# Sheet1.net
KiCad netlist of a schematic drawn in Altium Designer
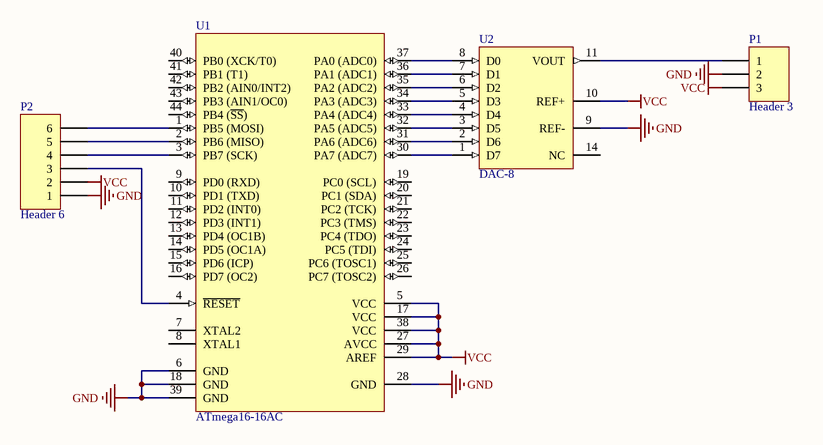
[diagram p0: Sheet1.SchDoc]

(export (version "E")
  (design (tool "Eeschema 10.0.6"))
  (components
    (comp (ref "P1")
      (value "Header 3")
      (footprint "HDR1X3")
      (description "Header, 3-Pin")
      (fields (field (name "PUBLISHER") "Altium Limited"))
      (libsource (lib "Miscellaneous Connectors") (part "Header 3"))
    )
    (comp (ref "P2")
      (value "Header 6")
      (footprint "HDR1X6")
      (description "Header, 6-Pin")
      (fields (field (name "PUBLISHER") "Altium Limited"))
      (libsource (lib "Miscellaneous Connectors") (part "Header 6"))
    )
    (comp (ref "U1")
      (value "ATmega16-16AC")
      (footprint "44A_N")
      (description "8-Bit AVR Microcontroller with 16K Bytes of In-System Programmable Flash Memory")
      (fields (field (name "PUBLISHER") "Altium Limited"))
      (libsource (lib "Atmel Microcontroller 8-Bit AVR") (part "ATmega16-16AC"))
    )
    (comp (ref "U2")
      (value "DAC-8")
      (footprint "SOT402-1_N")
      (description "Generic 8-Bit D/A Converter")
      (fields (field (name "PUBLISHER") "Altium Limited"))
      (libsource (lib "Miscellaneous Devices") (part "DAC-8"))
    )
  )
  (nets
    (net (code "1") (name "GND") (class "Default")
      (node (ref "P1") (pin "2") (pinfunction "2_2") (pintype "passive"))
      (node (ref "P2") (pin "1") (pinfunction "1_1") (pintype "passive"))
      (node (ref "U1") (pin "18") (pinfunction "GND_18") (pintype "power_in"))
      (node (ref "U1") (pin "28") (pinfunction "GND_28") (pintype "power_in"))
      (node (ref "U1") (pin "39") (pinfunction "GND_39") (pintype "power_in"))
      (node (ref "U1") (pin "6") (pinfunction "GND_6") (pintype "power_in"))
      (node (ref "U2") (pin "12") (pinfunction "GND_12") (pintype "power_in"))
      (node (ref "U2") (pin "9") (pinfunction "REF-_9") (pintype "passive"))
    )
    (net (code "2") (name "Net-(U1-PA0_(ADC0))") (class "Default")
      (node (ref "U1") (pin "37") (pinfunction "PA0_(ADC0)_37") (pintype "bidirectional"))
      (node (ref "U2") (pin "8") (pinfunction "D0_8") (pintype "input"))
    )
    (net (code "3") (name "Net-(U1-PA1_(ADC1))") (class "Default")
      (node (ref "U1") (pin "36") (pinfunction "PA1_(ADC1)_36") (pintype "bidirectional"))
      (node (ref "U2") (pin "7") (pinfunction "D1_7") (pintype "input"))
    )
    (net (code "4") (name "Net-(U1-PA2_(ADC2))") (class "Default")
      (node (ref "U1") (pin "35") (pinfunction "PA2_(ADC2)_35") (pintype "bidirectional"))
      (node (ref "U2") (pin "6") (pinfunction "D2_6") (pintype "input"))
    )
    (net (code "5") (name "Net-(U1-PA3_(ADC3))") (class "Default")
      (node (ref "U1") (pin "34") (pinfunction "PA3_(ADC3)_34") (pintype "bidirectional"))
      (node (ref "U2") (pin "5") (pinfunction "D3_5") (pintype "input"))
    )
    (net (code "6") (name "Net-(U1-PA4_(ADC4))") (class "Default")
      (node (ref "U1") (pin "33") (pinfunction "PA4_(ADC4)_33") (pintype "bidirectional"))
      (node (ref "U2") (pin "4") (pinfunction "D4_4") (pintype "input"))
    )
    (net (code "7") (name "Net-(U1-PA5_(ADC5))") (class "Default")
      (node (ref "U1") (pin "32") (pinfunction "PA5_(ADC5)_32") (pintype "bidirectional"))
      (node (ref "U2") (pin "3") (pinfunction "D5_3") (pintype "input"))
    )
    (net (code "8") (name "Net-(U1-PA6_(ADC6))") (class "Default")
      (node (ref "U1") (pin "31") (pinfunction "PA6_(ADC6)_31") (pintype "bidirectional"))
      (node (ref "U2") (pin "2") (pinfunction "D6_2") (pintype "input"))
    )
    (net (code "9") (name "Net-(U1-PA7_(ADC7))") (class "Default")
      (node (ref "U1") (pin "30") (pinfunction "PA7_(ADC7)_30") (pintype "bidirectional"))
      (node (ref "U2") (pin "1") (pinfunction "D7_1") (pintype "input"))
    )
    (net (code "10") (name "Net-(U1-PB5_(MOSI))") (class "Default")
      (node (ref "P2") (pin "6") (pinfunction "6_6") (pintype "passive"))
      (node (ref "U1") (pin "1") (pinfunction "PB5_(MOSI)_1") (pintype "bidirectional"))
    )
    (net (code "11") (name "Net-(U1-PB6_(MISO))") (class "Default")
      (node (ref "P2") (pin "5") (pinfunction "5_5") (pintype "passive"))
      (node (ref "U1") (pin "2") (pinfunction "PB6_(MISO)_2") (pintype "bidirectional"))
    )
    (net (code "12") (name "Net-(U1-PB7_(SCK))") (class "Default")
      (node (ref "P2") (pin "4") (pinfunction "4_4") (pintype "passive"))
      (node (ref "U1") (pin "3") (pinfunction "PB7_(SCK)_3") (pintype "bidirectional"))
    )
    (net (code "13") (name "Net-(U1-~{RESET})") (class "Default")
      (node (ref "P2") (pin "3") (pinfunction "3_3") (pintype "passive"))
      (node (ref "U1") (pin "4") (pinfunction "~{RESET}_4") (pintype "input"))
    )
    (net (code "14") (name "Net-(U2-VOUT)") (class "Default")
      (node (ref "P1") (pin "1") (pinfunction "1_1") (pintype "passive"))
      (node (ref "U2") (pin "11") (pinfunction "VOUT_11") (pintype "output"))
    )
    (net (code "15") (name "VCC") (class "Default")
      (node (ref "P1") (pin "3") (pinfunction "3_3") (pintype "passive"))
      (node (ref "P2") (pin "2") (pinfunction "2_2") (pintype "passive"))
      (node (ref "U1") (pin "17") (pinfunction "VCC_17") (pintype "power_in"))
      (node (ref "U1") (pin "27") (pinfunction "AVCC_27") (pintype "power_in"))
      (node (ref "U1") (pin "29") (pinfunction "AREF_29") (pintype "passive"))
      (node (ref "U1") (pin "38") (pinfunction "VCC_38") (pintype "power_in"))
      (node (ref "U1") (pin "5") (pinfunction "VCC_5") (pintype "power_in"))
      (node (ref "U2") (pin "10") (pinfunction "REF+_10") (pintype "passive"))
      (node (ref "U2") (pin "13") (pinfunction "VCC_13") (pintype "power_in"))
    )
    (net (code "16") (name "unconnected-(U1-PB0_(XCK{slash}T0)-Pad40)") (class "Default")
      (node (ref "U1") (pin "40") (pinfunction "PB0_(XCK/T0)_40") (pintype "bidirectional"))
    )
    (net (code "17") (name "unconnected-(U1-PB1_(T1)-Pad41)") (class "Default")
      (node (ref "U1") (pin "41") (pinfunction "PB1_(T1)_41") (pintype "bidirectional"))
    )
    (net (code "18") (name "unconnected-(U1-PB2_(AIN0{slash}INT2)-Pad42)") (class "Default")
      (node (ref "U1") (pin "42") (pinfunction "PB2_(AIN0/INT2)_42") (pintype "bidirectional"))
    )
    (net (code "19") (name "unconnected-(U1-PB3_(AIN1{slash}OC0)-Pad43)") (class "Default")
      (node (ref "U1") (pin "43") (pinfunction "PB3_(AIN1/OC0)_43") (pintype "bidirectional"))
    )
    (net (code "20") (name "unconnected-(U1-PB4_(~{SS})-Pad44)") (class "Default")
      (node (ref "U1") (pin "44") (pinfunction "PB4_(~{SS})_44") (pintype "bidirectional"))
    )
    (net (code "21") (name "unconnected-(U1-PC0_(SCL)-Pad19)") (class "Default")
      (node (ref "U1") (pin "19") (pinfunction "PC0_(SCL)_19") (pintype "bidirectional"))
    )
    (net (code "22") (name "unconnected-(U1-PC1_(SDA)-Pad20)") (class "Default")
      (node (ref "U1") (pin "20") (pinfunction "PC1_(SDA)_20") (pintype "bidirectional"))
    )
    (net (code "23") (name "unconnected-(U1-PC2_(TCK)-Pad21)") (class "Default")
      (node (ref "U1") (pin "21") (pinfunction "PC2_(TCK)_21") (pintype "bidirectional"))
    )
    (net (code "24") (name "unconnected-(U1-PC3_(TMS)-Pad22)") (class "Default")
      (node (ref "U1") (pin "22") (pinfunction "PC3_(TMS)_22") (pintype "bidirectional"))
    )
    (net (code "25") (name "unconnected-(U1-PC4_(TDO)-Pad23)") (class "Default")
      (node (ref "U1") (pin "23") (pinfunction "PC4_(TDO)_23") (pintype "bidirectional"))
    )
    (net (code "26") (name "unconnected-(U1-PC5_(TDI)-Pad24)") (class "Default")
      (node (ref "U1") (pin "24") (pinfunction "PC5_(TDI)_24") (pintype "bidirectional"))
    )
    (net (code "27") (name "unconnected-(U1-PC6_(TOSC1)-Pad25)") (class "Default")
      (node (ref "U1") (pin "25") (pinfunction "PC6_(TOSC1)_25") (pintype "bidirectional"))
    )
    (net (code "28") (name "unconnected-(U1-PC7_(TOSC2)-Pad26)") (class "Default")
      (node (ref "U1") (pin "26") (pinfunction "PC7_(TOSC2)_26") (pintype "bidirectional"))
    )
    (net (code "29") (name "unconnected-(U1-PD0_(RXD)-Pad9)") (class "Default")
      (node (ref "U1") (pin "9") (pinfunction "PD0_(RXD)_9") (pintype "bidirectional"))
    )
    (net (code "30") (name "unconnected-(U1-PD1_(TXD)-Pad10)") (class "Default")
      (node (ref "U1") (pin "10") (pinfunction "PD1_(TXD)_10") (pintype "bidirectional"))
    )
    (net (code "31") (name "unconnected-(U1-PD2_(INT0)-Pad11)") (class "Default")
      (node (ref "U1") (pin "11") (pinfunction "PD2_(INT0)_11") (pintype "bidirectional"))
    )
    (net (code "32") (name "unconnected-(U1-PD3_(INT1)-Pad12)") (class "Default")
      (node (ref "U1") (pin "12") (pinfunction "PD3_(INT1)_12") (pintype "bidirectional"))
    )
    (net (code "33") (name "unconnected-(U1-PD4_(OC1B)-Pad13)") (class "Default")
      (node (ref "U1") (pin "13") (pinfunction "PD4_(OC1B)_13") (pintype "bidirectional"))
    )
    (net (code "34") (name "unconnected-(U1-PD5_(OC1A)-Pad14)") (class "Default")
      (node (ref "U1") (pin "14") (pinfunction "PD5_(OC1A)_14") (pintype "bidirectional"))
    )
    (net (code "35") (name "unconnected-(U1-PD6_(ICP)-Pad15)") (class "Default")
      (node (ref "U1") (pin "15") (pinfunction "PD6_(ICP)_15") (pintype "bidirectional"))
    )
    (net (code "36") (name "unconnected-(U1-PD7_(OC2)-Pad16)") (class "Default")
      (node (ref "U1") (pin "16") (pinfunction "PD7_(OC2)_16") (pintype "bidirectional"))
    )
    (net (code "37") (name "unconnected-(U1-XTAL1-Pad8)") (class "Default")
      (node (ref "U1") (pin "8") (pinfunction "XTAL1_8") (pintype "passive"))
    )
    (net (code "38") (name "unconnected-(U1-XTAL2-Pad7)") (class "Default")
      (node (ref "U1") (pin "7") (pinfunction "XTAL2_7") (pintype "passive"))
    )
    (net (code "39") (name "unconnected-(U2-NC-Pad14)") (class "Default")
      (node (ref "U2") (pin "14") (pinfunction "NC_14") (pintype "passive"))
    )
  )
)
